# Integrated_Main_Driver_Board-06-Power_Su.net
KiCad netlist of a schematic drawn in Altium Designer
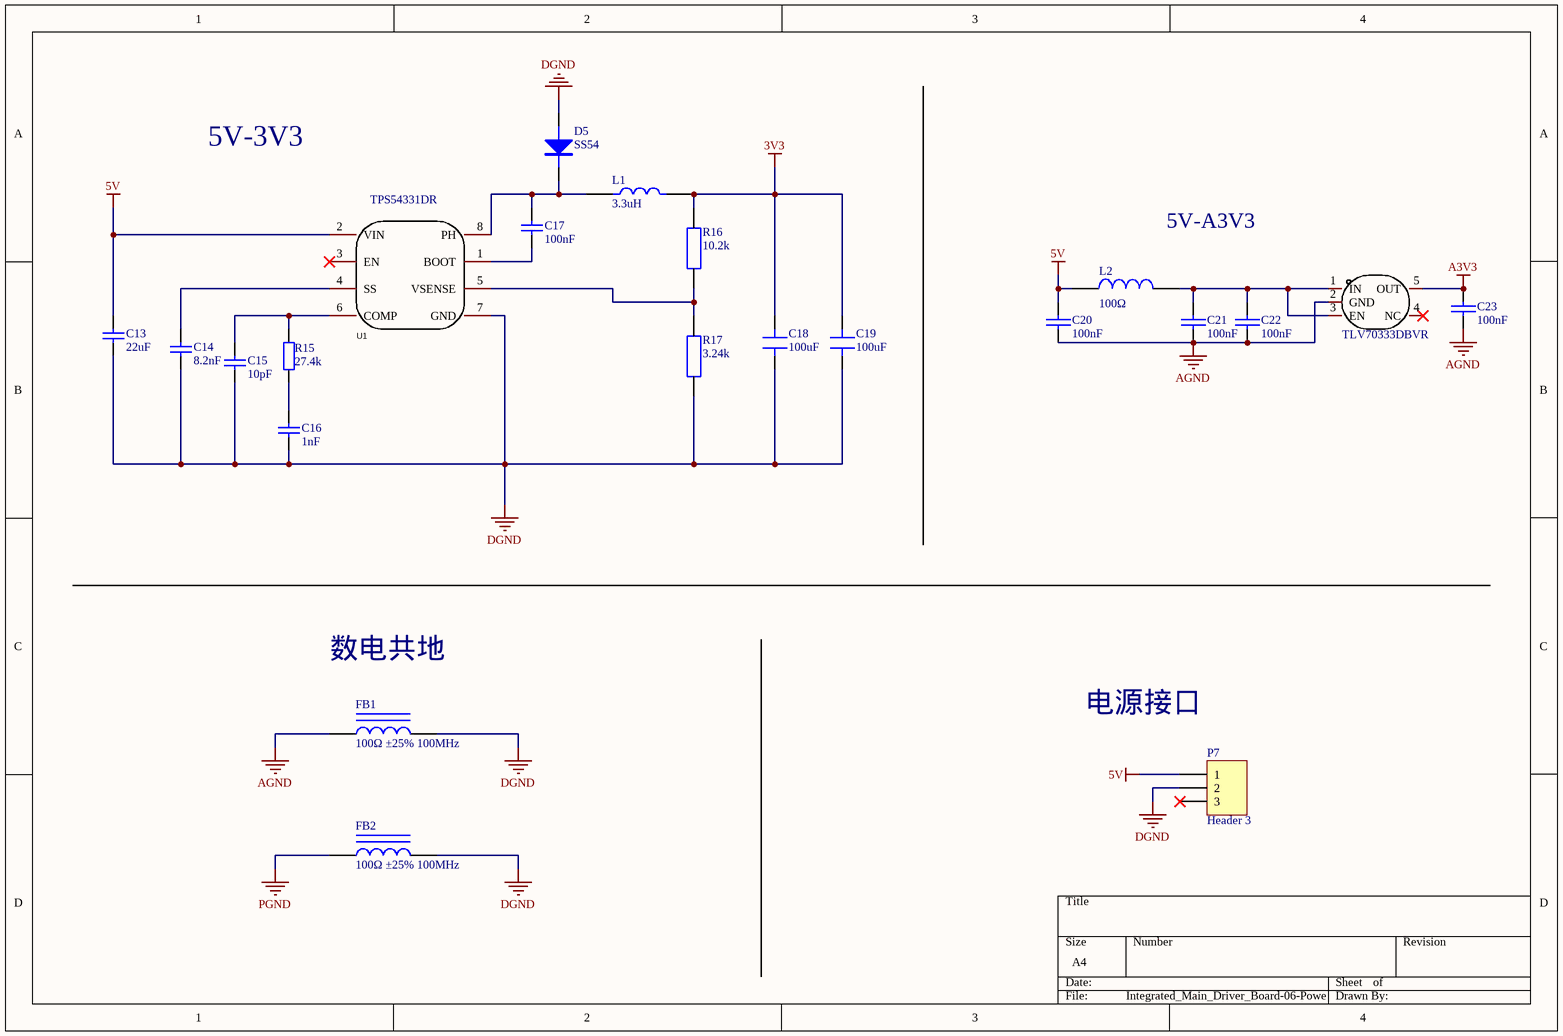
[diagram p0: Integrated_Main_Driver_Board-06-Power Supply Circuit -20230110.SchDoc]

(export (version "E")
  (design (tool "Eeschema 10.0.6"))
  (components
    (comp (ref "C13")
      (value "22uF")
      (footprint "0805C")
      (description "贴片电容")
      (libsource (lib "Miscellaneous Devices LC-2022") (part "0805 10uF (106) 10% 25V"))
    )
    (comp (ref "C14")
      (value "8.2nF")
      (footprint "0402C")
      (description "贴片电容")
      (libsource (lib "Miscellaneous Devices LC-2022") (part "0805 2.0pF (2R0) 0.25pF 50V"))
    )
    (comp (ref "C15")
      (value "10pF")
      (footprint "0402C")
      (description "贴片电容")
      (libsource (lib "Miscellaneous Devices LC-2022") (part "0805 10uF (106) 10% 25V"))
    )
    (comp (ref "C16")
      (value "1nF")
      (footprint "0402C")
      (description "贴片电容")
      (libsource (lib "Miscellaneous Devices LC-2022") (part "0805 10uF (106) 10% 25V"))
    )
    (comp (ref "C17")
      (value "100nF")
      (footprint "0402C")
      (description "贴片电容")
      (libsource (lib "Miscellaneous Devices LC-2022") (part "0805 100nF(104) 10% 50V"))
    )
    (comp (ref "C18") (value "100uF") (footprint "1206C") (libsource (lib "主控板元件库") (part "47uF 0805")))
    (comp (ref "C19") (value "100uF") (footprint "1206C") (libsource (lib "主控板元件库") (part "47uF 0805")))
    (comp (ref "C20")
      (value "100nF")
      (footprint "0402C")
      (description "无极性电容")
      (libsource (lib "电容") (part "CAP"))
    )
    (comp (ref "C21")
      (value "100nF")
      (footprint "0402C")
      (description "无极性电容")
      (libsource (lib "电容") (part "CAP"))
    )
    (comp (ref "C22")
      (value "100nF")
      (footprint "0402C")
      (description "无极性电容")
      (libsource (lib "电容") (part "CAP"))
    )
    (comp (ref "C23")
      (value "100nF")
      (footprint "0402C")
      (description "无极性电容")
      (libsource (lib "电容") (part "CAP"))
    )
    (comp (ref "D5")
      (value "SS54")
      (footprint "DO-15")
      (description "普通二极管")
      (libsource (lib "二极管") (part "DIODE"))
    )
    (comp (ref "FB1")
      (value "100Ω ±25% 100MHz")
      (footprint "磁珠0402")
      (description "贴片磁珠")
      (libsource (lib "Miscellaneous Devices LC-2022") (part "0805 100Ω 25% 100MHz"))
    )
    (comp (ref "FB2")
      (value "100Ω ±25% 100MHz")
      (footprint "磁珠0402")
      (description "贴片磁珠")
      (libsource (lib "Miscellaneous Devices LC-2022") (part "0805 100Ω 25% 100MHz"))
    )
    (comp (ref "L1") (value "3.3uH") (footprint "0630L") (libsource (lib "主控板元件库") (part "15uH 电感")))
    (comp (ref "L2")
      (value "100Ω")
      (footprint "0805L")
      (description "INDUCTOR")
      (libsource (lib "电感") (part "INDUCTOR"))
    )
    (comp (ref "P7")
      (value "Header 3")
      (footprint "3V-12V to 5.00V @ 3A")
      (description "Header, 3-Pin")
      (fields (field (name "PUBLISHER") "Altium Limited"))
      (libsource (lib "Miscellaneous Connectors") (part "Header 3"))
    )
    (comp (ref "R15")
      (value "27.4k")
      (footprint "0402R")
      (description "贴片电阻")
      (libsource (lib "Miscellaneous Devices LC-2022") (part "0805 10MΩ (1005) 1%"))
    )
    (comp (ref "R16") (value "10.2k") (footprint "0402R") (libsource (lib "主控板元件库") (part "10K 0805")))
    (comp (ref "R17") (value "3.24k") (footprint "0402R") (libsource (lib "主控板元件库") (part "10K 0805")))
    (comp (ref "U1")
      (value "TPS54331DR")
      (footprint "TPS54331DR")
      (fields (field (name "MANUFACTURER") "TI(德州仪器)"))
      (libsource (lib "主控板元件库") (part "TPS54331DR"))
    )
    (comp (ref "U2")
      (value "TLV70333DBVR")
      (footprint "TLV70333")
      (fields (field (name "MANUFACTURER") "TI(德州仪器)"))
      (libsource (lib "原理图库") (part "TLV70333DBVR"))
    )
  )
  (nets
    (net (code "1") (name "3V3") (class "Default")
      (node (ref "C18") (pin "2") (pinfunction "2_2") (pintype "passive"))
      (node (ref "C19") (pin "2") (pinfunction "2_2") (pintype "passive"))
      (node (ref "L1") (pin "2") (pinfunction "5_2") (pintype "passive"))
      (node (ref "R16") (pin "2") (pinfunction "2_2") (pintype "passive"))
    )
    (net (code "2") (name "5V") (class "Default")
      (node (ref "C13") (pin "2") (pinfunction "2_2") (pintype "passive"))
      (node (ref "C20") (pin "2") (pinfunction "2_2") (pintype "passive"))
      (node (ref "L2") (pin "1") (pinfunction "1_1") (pintype "passive"))
      (node (ref "P7") (pin "1") (pinfunction "1_1") (pintype "passive"))
      (node (ref "U1") (pin "2") (pinfunction "VIN_2") (pintype "passive"))
    )
    (net (code "3") (name "A3V3") (class "Default")
      (node (ref "C23") (pin "2") (pinfunction "2_2") (pintype "passive"))
      (node (ref "U2") (pin "5") (pinfunction "OUT_5") (pintype "passive"))
    )
    (net (code "4") (name "AGND") (class "Default")
      (node (ref "C20") (pin "1") (pinfunction "1_1") (pintype "passive"))
      (node (ref "C21") (pin "1") (pinfunction "1_1") (pintype "passive"))
      (node (ref "C22") (pin "1") (pinfunction "1_1") (pintype "passive"))
      (node (ref "C23") (pin "1") (pinfunction "1_1") (pintype "passive"))
      (node (ref "FB1") (pin "1") (pinfunction "1_1") (pintype "passive"))
      (node (ref "U2") (pin "2") (pinfunction "GND_2") (pintype "passive"))
    )
    (net (code "5") (name "DGND") (class "Default")
      (node (ref "C13") (pin "1") (pinfunction "1_1") (pintype "passive"))
      (node (ref "C14") (pin "2") (pinfunction "2_2") (pintype "passive"))
      (node (ref "C15") (pin "1") (pinfunction "1_1") (pintype "passive"))
      (node (ref "C16") (pin "1") (pinfunction "1_1") (pintype "passive"))
      (node (ref "C18") (pin "1") (pinfunction "1_1") (pintype "passive"))
      (node (ref "C19") (pin "1") (pinfunction "1_1") (pintype "passive"))
      (node (ref "D5") (pin "A") (pinfunction "A_A") (pintype "passive"))
      (node (ref "FB1") (pin "2") (pinfunction "2_2") (pintype "passive"))
      (node (ref "FB2") (pin "2") (pinfunction "2_2") (pintype "passive"))
      (node (ref "P7") (pin "2") (pinfunction "2_2") (pintype "passive"))
      (node (ref "R17") (pin "1") (pinfunction "1_1") (pintype "passive"))
      (node (ref "U1") (pin "7") (pinfunction "GND_7") (pintype "passive"))
    )
    (net (code "6") (name "Net-(C16-Pad2)") (class "Default")
      (node (ref "C16") (pin "2") (pinfunction "2_2") (pintype "passive"))
      (node (ref "R15") (pin "1") (pinfunction "1_1") (pintype "passive"))
    )
    (net (code "7") (name "Net-(L1-4)") (class "Default")
      (node (ref "C17") (pin "2") (pinfunction "2_2") (pintype "passive"))
      (node (ref "D5") (pin "K") (pinfunction "K_K") (pintype "passive"))
      (node (ref "L1") (pin "1") (pinfunction "4_1") (pintype "passive"))
      (node (ref "U1") (pin "8") (pinfunction "PH_8") (pintype "passive"))
    )
    (net (code "8") (name "Net-(U1-BOOT)") (class "Default")
      (node (ref "C17") (pin "1") (pinfunction "1_1") (pintype "passive"))
      (node (ref "U1") (pin "1") (pinfunction "BOOT_1") (pintype "passive"))
    )
    (net (code "9") (name "Net-(U1-COMP)") (class "Default")
      (node (ref "C15") (pin "2") (pinfunction "2_2") (pintype "passive"))
      (node (ref "R15") (pin "2") (pinfunction "2_2") (pintype "passive"))
      (node (ref "U1") (pin "6") (pinfunction "COMP_6") (pintype "passive"))
    )
    (net (code "10") (name "Net-(U1-SS)") (class "Default")
      (node (ref "C14") (pin "1") (pinfunction "1_1") (pintype "passive"))
      (node (ref "U1") (pin "4") (pinfunction "SS_4") (pintype "passive"))
    )
    (net (code "11") (name "Net-(U1-VSENSE)") (class "Default")
      (node (ref "R16") (pin "1") (pinfunction "1_1") (pintype "passive"))
      (node (ref "R17") (pin "2") (pinfunction "2_2") (pintype "passive"))
      (node (ref "U1") (pin "5") (pinfunction "VSENSE_5") (pintype "passive"))
    )
    (net (code "12") (name "Net-(U2-EN)") (class "Default")
      (node (ref "C21") (pin "2") (pinfunction "2_2") (pintype "passive"))
      (node (ref "C22") (pin "2") (pinfunction "2_2") (pintype "passive"))
      (node (ref "L2") (pin "2") (pinfunction "2_2") (pintype "passive"))
      (node (ref "U2") (pin "1") (pinfunction "IN_1") (pintype "passive"))
      (node (ref "U2") (pin "3") (pinfunction "EN_3") (pintype "passive"))
    )
    (net (code "13") (name "PGND") (class "Default")
      (node (ref "FB2") (pin "1") (pinfunction "1_1") (pintype "passive"))
    )
    (net (code "14") (name "unconnected-(P7-Pad3)") (class "Default")
      (node (ref "P7") (pin "3") (pinfunction "3_3") (pintype "passive+no_connect"))
    )
    (net (code "15") (name "unconnected-(U1-EN-Pad3)") (class "Default")
      (node (ref "U1") (pin "3") (pinfunction "EN_3") (pintype "passive+no_connect"))
    )
    (net (code "16") (name "unconnected-(U2-NC-Pad4)") (class "Default")
      (node (ref "U2") (pin "4") (pinfunction "NC_4") (pintype "passive+no_connect"))
    )
  )
)
